# IO-testing-mezzanine.net
KiCad netlist of a schematic drawn in Altium Designer
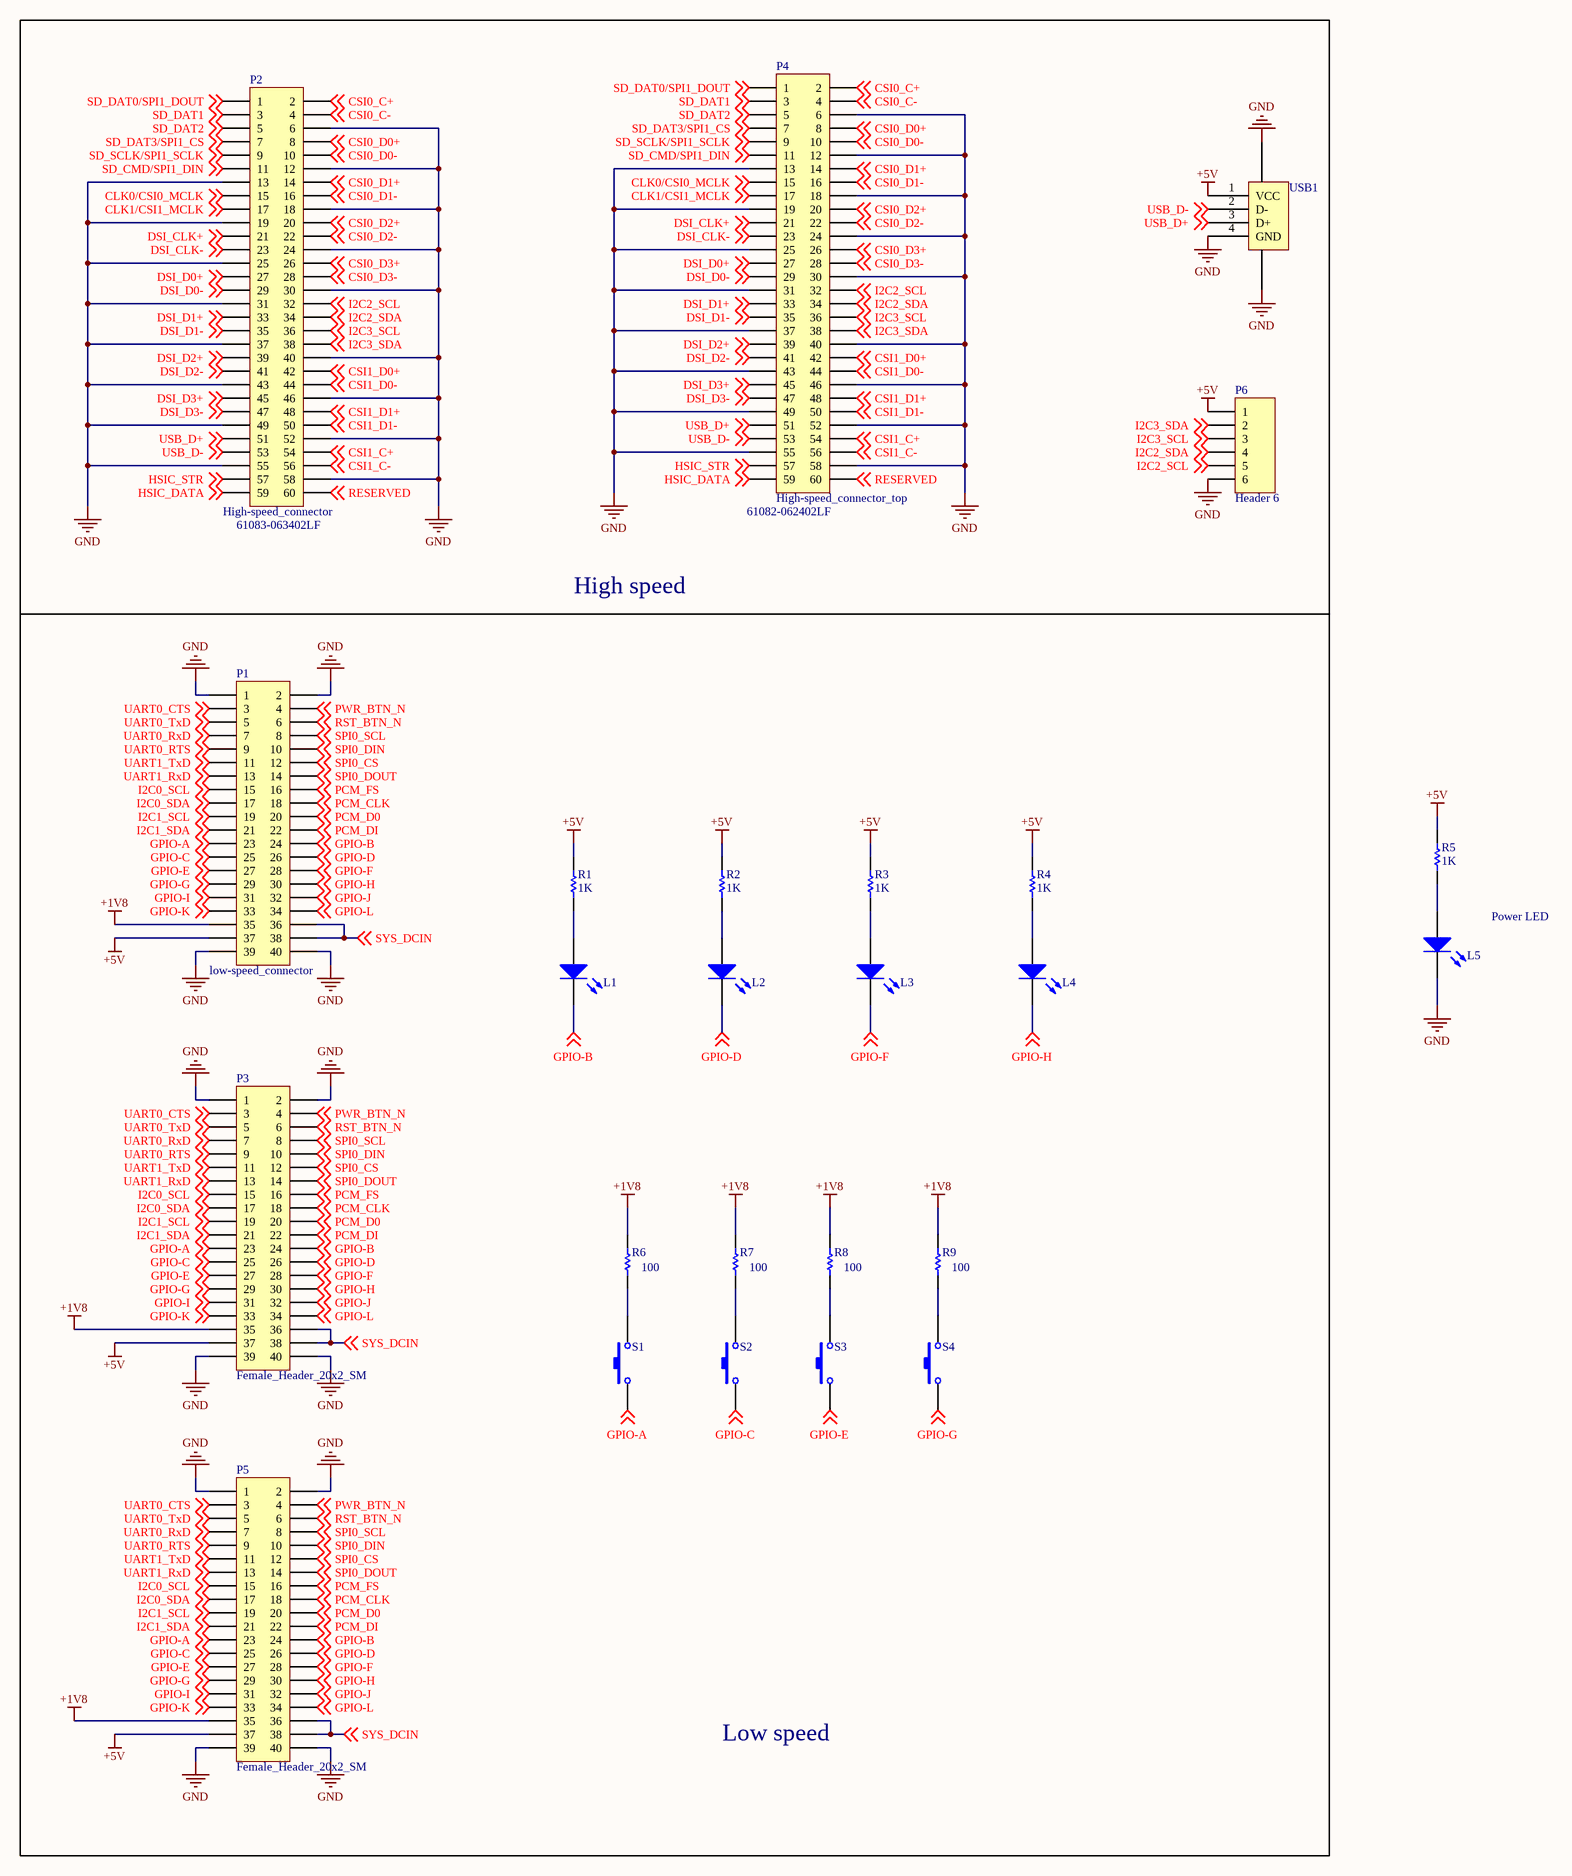
[diagram p0: IO-testing-mezzanine.SchDoc]

(export (version "E")
  (design (tool "Eeschema 10.0.6"))
  (components
    (comp (ref "L1")
      (value "~")
      (footprint "LED_0603")
      (description "LED BLUE CLEAR 0603 SMD")
      (fields
        (field (name "MANUFACTURER") "Lite-On Inc.")
        (field (name "MANUFACTURER PART NUMBER") "LTST-C193TBKT-5A")
      )
      (libsource (lib "IO-testing-mezzanine") (part "LTST-C193TBKT-5A"))
    )
    (comp (ref "L2")
      (value "~")
      (footprint "LED_0603")
      (description "LED BLUE CLEAR 0603 SMD")
      (fields
        (field (name "MANUFACTURER") "Lite-On Inc.")
        (field (name "MANUFACTURER PART NUMBER") "LTST-C193TBKT-5A")
      )
      (libsource (lib "IO-testing-mezzanine") (part "LTST-C193TBKT-5A"))
    )
    (comp (ref "L3")
      (value "~")
      (footprint "LED_0603")
      (description "LED BLUE CLEAR 0603 SMD")
      (fields
        (field (name "MANUFACTURER") "Lite-On Inc.")
        (field (name "MANUFACTURER PART NUMBER") "LTST-C193TBKT-5A")
      )
      (libsource (lib "IO-testing-mezzanine") (part "LTST-C193TBKT-5A"))
    )
    (comp (ref "L4")
      (value "~")
      (footprint "LED_0603")
      (description "LED BLUE CLEAR 0603 SMD")
      (fields
        (field (name "MANUFACTURER") "Lite-On Inc.")
        (field (name "MANUFACTURER PART NUMBER") "LTST-C193TBKT-5A")
      )
      (libsource (lib "IO-testing-mezzanine") (part "LTST-C193TBKT-5A"))
    )
    (comp (ref "L5")
      (value "~")
      (footprint "LED_0603")
      (description "LED BLUE CLEAR 0603 SMD")
      (fields
        (field (name "MANUFACTURER") "Lite-On Inc.")
        (field (name "MANUFACTURER PART NUMBER") "LTST-C193TBKT-5A")
      )
      (libsource (lib "IO-testing-mezzanine") (part "LTST-C193TBKT-5A"))
    )
    (comp (ref "P1")
      (value "low-speed_connector")
      (footprint "low-speed_connector_SM")
      (libsource (lib "mezza") (part "low-speed_connector"))
    )
    (comp (ref "P2")
      (value "High-speed_connector")
      (footprint "high-speed_connector")
      (fields (field (name "PARTNUMBER") "61083-063402LF"))
      (libsource (lib "mezza") (part "High-speed_connector"))
    )
    (comp (ref "P3")
      (value "Female_Header_20x2_SM")
      (footprint "Female_Header_20x2_SM")
      (libsource (lib "IO-testing-mezzanine") (part "Female_Header_20x2_SM"))
    )
    (comp (ref "P4")
      (value "High-speed_connector_top")
      (footprint "high-speed_connector_top")
      (fields
        (field (name "MANUFACTURER") "Amphenol FCI")
        (field (name "MANUFACTURER PART NUMBER") "61082-062402LF")
        (field (name "PARTNUMBER") "61082-062402LF")
      )
      (libsource (lib "IO-testing-mezzanine") (part "High-speed_connector_top"))
    )
    (comp (ref "P5")
      (value "Female_Header_20x2_SM")
      (footprint "low-speed_connector_SM_top")
      (libsource (lib "IO-testing-mezzanine") (part "Female_Header_20x2_SM"))
    )
    (comp (ref "P6")
      (value "Header 6")
      (footprint "HDR1X6")
      (description "Header, 6-Pin")
      (fields (field (name "PUBLISHER") "Altium Limited"))
      (libsource (lib "Miscellaneous Connectors") (part "Header 6"))
    )
    (comp (ref "R1")
      (value "1K")
      (footprint "0603")
      (description "Resistor")
      (fields
        (field (name "PARTNUMBER") "RC0603JR-071KL")
        (field (name "Comment") "Res1")
        (field (name "PUBLISHER") "Altium Limited")
      )
      (libsource (lib "IO-testing-mezzanine") (part "Res1"))
    )
    (comp (ref "R2")
      (value "1K")
      (footprint "0603")
      (description "Resistor")
      (fields
        (field (name "PARTNUMBER") "RC0603JR-071KL")
        (field (name "Comment") "Res1")
        (field (name "PUBLISHER") "Altium Limited")
      )
      (libsource (lib "IO-testing-mezzanine") (part "Res1"))
    )
    (comp (ref "R3")
      (value "1K")
      (footprint "0603")
      (description "Resistor")
      (fields
        (field (name "PARTNUMBER") "RC0603JR-071KL")
        (field (name "Comment") "Res1")
        (field (name "PUBLISHER") "Altium Limited")
      )
      (libsource (lib "IO-testing-mezzanine") (part "Res1"))
    )
    (comp (ref "R4")
      (value "1K")
      (footprint "0603")
      (description "Resistor")
      (fields
        (field (name "PARTNUMBER") "RC0603JR-071KL")
        (field (name "Comment") "Res1")
        (field (name "PUBLISHER") "Altium Limited")
      )
      (libsource (lib "IO-testing-mezzanine") (part "Res1"))
    )
    (comp (ref "R5")
      (value "1K")
      (footprint "0603")
      (description "Resistor")
      (fields
        (field (name "PARTNUMBER") "RC0603JR-071KL")
        (field (name "Comment") "Res1")
        (field (name "PUBLISHER") "Altium Limited")
      )
      (libsource (lib "IO-testing-mezzanine") (part "Res1"))
    )
    (comp (ref "R6")
      (value "100")
      (footprint "0603")
      (description "Resistor")
      (fields
        (field (name "MANUFACTURER") "Yageo")
        (field (name "MANUFACTURER PART NUMBER") "RC0603JR-07100RL")
      )
      (libsource (lib "IO-testing-mezzanine") (part "Res1"))
    )
    (comp (ref "R7")
      (value "100")
      (footprint "0603")
      (description "Resistor")
      (fields
        (field (name "MANUFACTURER") "Yageo")
        (field (name "MANUFACTURER PART NUMBER") "RC0603JR-07100RL")
      )
      (libsource (lib "IO-testing-mezzanine") (part "Res1"))
    )
    (comp (ref "R8")
      (value "100")
      (footprint "0603")
      (description "Resistor")
      (fields
        (field (name "MANUFACTURER") "Yageo")
        (field (name "MANUFACTURER PART NUMBER") "RC0603JR-07100RL")
      )
      (libsource (lib "IO-testing-mezzanine") (part "Res1"))
    )
    (comp (ref "R9")
      (value "100")
      (footprint "0603")
      (description "Resistor")
      (fields
        (field (name "MANUFACTURER") "Yageo")
        (field (name "MANUFACTURER PART NUMBER") "RC0603JR-07100RL")
      )
      (libsource (lib "IO-testing-mezzanine") (part "Res1"))
    )
    (comp (ref "S1")
      (value "SW-PB")
      (footprint "SW-PB")
      (description "Switch")
      (fields
        (field (name "MANUFACTURER") "C&K")
        (field (name "MANUFACTURER PART NUMBER") "KSR223GLFG")
        (field (name "PUBLISHER") "Altium Limited")
      )
      (libsource (lib "IO-testing-mezzanine") (part "SW-PB"))
    )
    (comp (ref "S2")
      (value "SW-PB")
      (footprint "SW-PB")
      (description "Switch")
      (fields
        (field (name "MANUFACTURER") "C&K")
        (field (name "MANUFACTURER PART NUMBER") "KSR223GLFG")
        (field (name "PUBLISHER") "Altium Limited")
      )
      (libsource (lib "IO-testing-mezzanine") (part "SW-PB"))
    )
    (comp (ref "S3")
      (value "SW-PB")
      (footprint "SW-PB")
      (description "Switch")
      (fields
        (field (name "MANUFACTURER") "C&K")
        (field (name "MANUFACTURER PART NUMBER") "KSR223GLFG")
        (field (name "PUBLISHER") "Altium Limited")
      )
      (libsource (lib "IO-testing-mezzanine") (part "SW-PB"))
    )
    (comp (ref "S4")
      (value "SW-PB")
      (footprint "SW-PB")
      (description "Switch")
      (fields
        (field (name "MANUFACTURER") "C&K")
        (field (name "MANUFACTURER PART NUMBER") "KSR223GLFG")
        (field (name "PUBLISHER") "Altium Limited")
      )
      (libsource (lib "IO-testing-mezzanine") (part "SW-PB"))
    )
    (comp (ref "USB1")
      (value "USB")
      (footprint "USB_a")
      (fields (field (name "PARTNUMBER") "USB-A-S-F-W-SM2") (field (name "MANUFACTURER") "Samtec Inc."))
      (libsource (lib "IO-testing-mezzanine") (part "USB"))
    )
  )
  (nets
    (net (code "1") (name "+1V8") (class "Default")
      (node (ref "P1") (pin "35") (pinfunction "35_35") (pintype "passive"))
      (node (ref "P3") (pin "35") (pinfunction "35_35") (pintype "passive"))
      (node (ref "P5") (pin "35") (pinfunction "35_35") (pintype "passive"))
      (node (ref "R6") (pin "2") (pinfunction "2_2") (pintype "passive"))
      (node (ref "R7") (pin "2") (pinfunction "2_2") (pintype "passive"))
      (node (ref "R8") (pin "2") (pinfunction "2_2") (pintype "passive"))
      (node (ref "R9") (pin "2") (pinfunction "2_2") (pintype "passive"))
    )
    (net (code "2") (name "+5V") (class "Default")
      (node (ref "P1") (pin "37") (pinfunction "37_37") (pintype "passive"))
      (node (ref "P3") (pin "37") (pinfunction "37_37") (pintype "passive"))
      (node (ref "P5") (pin "37") (pinfunction "37_37") (pintype "passive"))
      (node (ref "P6") (pin "1") (pinfunction "1_1") (pintype "passive"))
      (node (ref "R1") (pin "2") (pinfunction "2_2") (pintype "passive"))
      (node (ref "R2") (pin "2") (pinfunction "2_2") (pintype "passive"))
      (node (ref "R3") (pin "2") (pinfunction "2_2") (pintype "passive"))
      (node (ref "R4") (pin "2") (pinfunction "2_2") (pintype "passive"))
      (node (ref "R5") (pin "2") (pinfunction "2_2") (pintype "passive"))
      (node (ref "USB1") (pin "1") (pinfunction "VCC_1") (pintype "power_in"))
    )
    (net (code "3") (name "CLK0{slash}CSI0_MCLK") (class "Default")
      (node (ref "P2") (pin "15") (pinfunction "15_15") (pintype "passive"))
      (node (ref "P4") (pin "15") (pinfunction "15_15") (pintype "passive"))
    )
    (net (code "4") (name "CLK1{slash}CSI1_MCLK") (class "Default")
      (node (ref "P2") (pin "17") (pinfunction "17_17") (pintype "passive"))
      (node (ref "P4") (pin "17") (pinfunction "17_17") (pintype "passive"))
    )
    (net (code "5") (name "CSI0_C+") (class "Default")
      (node (ref "P2") (pin "2") (pinfunction "2_2") (pintype "passive"))
      (node (ref "P4") (pin "2") (pinfunction "2_2") (pintype "passive"))
    )
    (net (code "6") (name "CSI0_C-") (class "Default")
      (node (ref "P2") (pin "4") (pinfunction "4_4") (pintype "passive"))
      (node (ref "P4") (pin "4") (pinfunction "4_4") (pintype "passive"))
    )
    (net (code "7") (name "CSI0_D0+") (class "Default")
      (node (ref "P2") (pin "8") (pinfunction "8_8") (pintype "passive"))
      (node (ref "P4") (pin "8") (pinfunction "8_8") (pintype "passive"))
    )
    (net (code "8") (name "CSI0_D0-") (class "Default")
      (node (ref "P2") (pin "10") (pinfunction "10_10") (pintype "passive"))
      (node (ref "P4") (pin "10") (pinfunction "10_10") (pintype "passive"))
    )
    (net (code "9") (name "CSI0_D1+") (class "Default")
      (node (ref "P2") (pin "14") (pinfunction "14_14") (pintype "passive"))
      (node (ref "P4") (pin "14") (pinfunction "14_14") (pintype "passive"))
    )
    (net (code "10") (name "CSI0_D1-") (class "Default")
      (node (ref "P2") (pin "16") (pinfunction "16_16") (pintype "passive"))
      (node (ref "P4") (pin "16") (pinfunction "16_16") (pintype "passive"))
    )
    (net (code "11") (name "CSI0_D2+") (class "Default")
      (node (ref "P2") (pin "20") (pinfunction "20_20") (pintype "passive"))
      (node (ref "P4") (pin "20") (pinfunction "20_20") (pintype "passive"))
    )
    (net (code "12") (name "CSI0_D2-") (class "Default")
      (node (ref "P2") (pin "22") (pinfunction "22_22") (pintype "passive"))
      (node (ref "P4") (pin "22") (pinfunction "22_22") (pintype "passive"))
    )
    (net (code "13") (name "CSI0_D3+") (class "Default")
      (node (ref "P2") (pin "26") (pinfunction "26_26") (pintype "passive"))
      (node (ref "P4") (pin "26") (pinfunction "26_26") (pintype "passive"))
    )
    (net (code "14") (name "CSI0_D3-") (class "Default")
      (node (ref "P2") (pin "28") (pinfunction "28_28") (pintype "passive"))
      (node (ref "P4") (pin "28") (pinfunction "28_28") (pintype "passive"))
    )
    (net (code "15") (name "CSI1_C+") (class "Default")
      (node (ref "P2") (pin "54") (pinfunction "54_54") (pintype "passive"))
      (node (ref "P4") (pin "54") (pinfunction "54_54") (pintype "passive"))
    )
    (net (code "16") (name "CSI1_C-") (class "Default")
      (node (ref "P2") (pin "56") (pinfunction "56_56") (pintype "passive"))
      (node (ref "P4") (pin "56") (pinfunction "56_56") (pintype "passive"))
    )
    (net (code "17") (name "CSI1_D0+") (class "Default")
      (node (ref "P2") (pin "42") (pinfunction "42_42") (pintype "passive"))
      (node (ref "P4") (pin "42") (pinfunction "42_42") (pintype "passive"))
    )
    (net (code "18") (name "CSI1_D0-") (class "Default")
      (node (ref "P2") (pin "44") (pinfunction "44_44") (pintype "passive"))
      (node (ref "P4") (pin "44") (pinfunction "44_44") (pintype "passive"))
    )
    (net (code "19") (name "CSI1_D1+") (class "Default")
      (node (ref "P2") (pin "48") (pinfunction "48_48") (pintype "passive"))
      (node (ref "P4") (pin "48") (pinfunction "48_48") (pintype "passive"))
    )
    (net (code "20") (name "CSI1_D1-") (class "Default")
      (node (ref "P2") (pin "50") (pinfunction "50_50") (pintype "passive"))
      (node (ref "P4") (pin "50") (pinfunction "50_50") (pintype "passive"))
    )
    (net (code "21") (name "DSI_CLK+") (class "Default")
      (node (ref "P2") (pin "21") (pinfunction "21_21") (pintype "passive"))
      (node (ref "P4") (pin "21") (pinfunction "21_21") (pintype "passive"))
    )
    (net (code "22") (name "DSI_CLK-") (class "Default")
      (node (ref "P2") (pin "23") (pinfunction "23_23") (pintype "passive"))
      (node (ref "P4") (pin "23") (pinfunction "23_23") (pintype "passive"))
    )
    (net (code "23") (name "DSI_D0+") (class "Default")
      (node (ref "P2") (pin "27") (pinfunction "27_27") (pintype "passive"))
      (node (ref "P4") (pin "27") (pinfunction "27_27") (pintype "passive"))
    )
    (net (code "24") (name "DSI_D0-") (class "Default")
      (node (ref "P2") (pin "29") (pinfunction "29_29") (pintype "passive"))
      (node (ref "P4") (pin "29") (pinfunction "29_29") (pintype "passive"))
    )
    (net (code "25") (name "DSI_D1+") (class "Default")
      (node (ref "P2") (pin "33") (pinfunction "33_33") (pintype "passive"))
      (node (ref "P4") (pin "33") (pinfunction "33_33") (pintype "passive"))
    )
    (net (code "26") (name "DSI_D1-") (class "Default")
      (node (ref "P2") (pin "35") (pinfunction "35_35") (pintype "passive"))
      (node (ref "P4") (pin "35") (pinfunction "35_35") (pintype "passive"))
    )
    (net (code "27") (name "DSI_D2+") (class "Default")
      (node (ref "P2") (pin "39") (pinfunction "39_39") (pintype "passive"))
      (node (ref "P4") (pin "39") (pinfunction "39_39") (pintype "passive"))
    )
    (net (code "28") (name "DSI_D2-") (class "Default")
      (node (ref "P2") (pin "41") (pinfunction "41_41") (pintype "passive"))
      (node (ref "P4") (pin "41") (pinfunction "41_41") (pintype "passive"))
    )
    (net (code "29") (name "DSI_D3+") (class "Default")
      (node (ref "P2") (pin "45") (pinfunction "45_45") (pintype "passive"))
      (node (ref "P4") (pin "45") (pinfunction "45_45") (pintype "passive"))
    )
    (net (code "30") (name "DSI_D3-") (class "Default")
      (node (ref "P2") (pin "47") (pinfunction "47_47") (pintype "passive"))
      (node (ref "P4") (pin "47") (pinfunction "47_47") (pintype "passive"))
    )
    (net (code "31") (name "GND") (class "Default")
      (node (ref "L5") (pin "2") (pinfunction "K_2") (pintype "passive"))
      (node (ref "P1") (pin "1") (pinfunction "1_1") (pintype "passive"))
      (node (ref "P1") (pin "2") (pinfunction "2_2") (pintype "passive"))
      (node (ref "P1") (pin "39") (pinfunction "39_39") (pintype "passive"))
      (node (ref "P1") (pin "40") (pinfunction "40_40") (pintype "passive"))
      (node (ref "P2") (pin "12") (pinfunction "12_12") (pintype "passive"))
      (node (ref "P2") (pin "13") (pinfunction "13_13") (pintype "passive"))
      (node (ref "P2") (pin "18") (pinfunction "18_18") (pintype "passive"))
      (node (ref "P2") (pin "19") (pinfunction "19_19") (pintype "passive"))
      (node (ref "P2") (pin "24") (pinfunction "24_24") (pintype "passive"))
      (node (ref "P2") (pin "25") (pinfunction "25_25") (pintype "passive"))
      (node (ref "P2") (pin "30") (pinfunction "30_30") (pintype "passive"))
      (node (ref "P2") (pin "31") (pinfunction "31_31") (pintype "passive"))
      (node (ref "P2") (pin "37") (pinfunction "37_37") (pintype "passive"))
      (node (ref "P2") (pin "40") (pinfunction "40_40") (pintype "passive"))
      (node (ref "P2") (pin "43") (pinfunction "43_43") (pintype "passive"))
      (node (ref "P2") (pin "46") (pinfunction "46_46") (pintype "passive"))
      (node (ref "P2") (pin "49") (pinfunction "49_49") (pintype "passive"))
      (node (ref "P2") (pin "52") (pinfunction "52_52") (pintype "passive"))
      (node (ref "P2") (pin "55") (pinfunction "55_55") (pintype "passive"))
      (node (ref "P2") (pin "58") (pinfunction "58_58") (pintype "passive"))
      (node (ref "P2") (pin "6") (pinfunction "6_6") (pintype "passive"))
      (node (ref "P3") (pin "1") (pinfunction "1_1") (pintype "passive"))
      (node (ref "P3") (pin "2") (pinfunction "2_2") (pintype "passive"))
      (node (ref "P3") (pin "39") (pinfunction "39_39") (pintype "passive"))
      (node (ref "P3") (pin "40") (pinfunction "40_40") (pintype "passive"))
      (node (ref "P4") (pin "12") (pinfunction "12_12") (pintype "passive"))
      (node (ref "P4") (pin "13") (pinfunction "13_13") (pintype "passive"))
      (node (ref "P4") (pin "18") (pinfunction "18_18") (pintype "passive"))
      (node (ref "P4") (pin "19") (pinfunction "19_19") (pintype "passive"))
      (node (ref "P4") (pin "24") (pinfunction "24_24") (pintype "passive"))
      (node (ref "P4") (pin "25") (pinfunction "25_25") (pintype "passive"))
      (node (ref "P4") (pin "30") (pinfunction "30_30") (pintype "passive"))
      (node (ref "P4") (pin "31") (pinfunction "31_31") (pintype "passive"))
      (node (ref "P4") (pin "37") (pinfunction "37_37") (pintype "passive"))
      (node (ref "P4") (pin "40") (pinfunction "40_40") (pintype "passive"))
      (node (ref "P4") (pin "43") (pinfunction "43_43") (pintype "passive"))
      (node (ref "P4") (pin "46") (pinfunction "46_46") (pintype "passive"))
      (node (ref "P4") (pin "49") (pinfunction "49_49") (pintype "passive"))
      (node (ref "P4") (pin "52") (pinfunction "52_52") (pintype "passive"))
      (node (ref "P4") (pin "55") (pinfunction "55_55") (pintype "passive"))
      (node (ref "P4") (pin "58") (pinfunction "58_58") (pintype "passive"))
      (node (ref "P4") (pin "6") (pinfunction "6_6") (pintype "passive"))
      (node (ref "P5") (pin "1") (pinfunction "1_1") (pintype "passive"))
      (node (ref "P5") (pin "2") (pinfunction "2_2") (pintype "passive"))
      (node (ref "P5") (pin "39") (pinfunction "39_39") (pintype "passive"))
      (node (ref "P5") (pin "40") (pinfunction "40_40") (pintype "passive"))
      (node (ref "P6") (pin "6") (pinfunction "6_6") (pintype "passive"))
      (node (ref "USB1") (pin "4") (pinfunction "GND_4") (pintype "power_in"))
      (node (ref "USB1") (pin "5") (pinfunction "GND_5") (pintype "power_in"))
      (node (ref "USB1") (pin "6") (pinfunction "GND_6") (pintype "power_in"))
    )
    (net (code "32") (name "GPIO-A") (class "Default")
      (node (ref "P1") (pin "23") (pinfunction "23_23") (pintype "passive"))
      (node (ref "P3") (pin "23") (pinfunction "23_23") (pintype "passive"))
      (node (ref "P5") (pin "23") (pinfunction "23_23") (pintype "passive"))
      (node (ref "S1") (pin "1") (pinfunction "1_1") (pintype "passive"))
    )
    (net (code "33") (name "GPIO-B") (class "Default")
      (node (ref "L1") (pin "2") (pinfunction "K_2") (pintype "passive"))
      (node (ref "P1") (pin "24") (pinfunction "24_24") (pintype "passive"))
      (node (ref "P3") (pin "24") (pinfunction "24_24") (pintype "passive"))
      (node (ref "P5") (pin "24") (pinfunction "24_24") (pintype "passive"))
    )
    (net (code "34") (name "GPIO-C") (class "Default")
      (node (ref "P1") (pin "25") (pinfunction "25_25") (pintype "passive"))
      (node (ref "P3") (pin "25") (pinfunction "25_25") (pintype "passive"))
      (node (ref "P5") (pin "25") (pinfunction "25_25") (pintype "passive"))
      (node (ref "S2") (pin "1") (pinfunction "1_1") (pintype "passive"))
    )
    (net (code "35") (name "GPIO-D") (class "Default")
      (node (ref "L2") (pin "2") (pinfunction "K_2") (pintype "passive"))
      (node (ref "P1") (pin "26") (pinfunction "26_26") (pintype "passive"))
      (node (ref "P3") (pin "26") (pinfunction "26_26") (pintype "passive"))
      (node (ref "P5") (pin "26") (pinfunction "26_26") (pintype "passive"))
    )
    (net (code "36") (name "GPIO-E") (class "Default")
      (node (ref "P1") (pin "27") (pinfunction "27_27") (pintype "passive"))
      (node (ref "P3") (pin "27") (pinfunction "27_27") (pintype "passive"))
      (node (ref "P5") (pin "27") (pinfunction "27_27") (pintype "passive"))
      (node (ref "S3") (pin "1") (pinfunction "1_1") (pintype "passive"))
    )
    (net (code "37") (name "GPIO-F") (class "Default")
      (node (ref "L3") (pin "2") (pinfunction "K_2") (pintype "passive"))
      (node (ref "P1") (pin "28") (pinfunction "28_28") (pintype "passive"))
      (node (ref "P3") (pin "28") (pinfunction "28_28") (pintype "passive"))
      (node (ref "P5") (pin "28") (pinfunction "28_28") (pintype "passive"))
    )
    (net (code "38") (name "GPIO-G") (class "Default")
      (node (ref "P1") (pin "29") (pinfunction "29_29") (pintype "passive"))
      (node (ref "P3") (pin "29") (pinfunction "29_29") (pintype "passive"))
      (node (ref "P5") (pin "29") (pinfunction "29_29") (pintype "passive"))
      (node (ref "S4") (pin "1") (pinfunction "1_1") (pintype "passive"))
    )
    (net (code "39") (name "GPIO-H") (class "Default")
      (node (ref "L4") (pin "2") (pinfunction "K_2") (pintype "passive"))
      (node (ref "P1") (pin "30") (pinfunction "30_30") (pintype "passive"))
      (node (ref "P3") (pin "30") (pinfunction "30_30") (pintype "passive"))
      (node (ref "P5") (pin "30") (pinfunction "30_30") (pintype "passive"))
    )
    (net (code "40") (name "GPIO-I") (class "Default")
      (node (ref "P1") (pin "31") (pinfunction "31_31") (pintype "passive"))
      (node (ref "P3") (pin "31") (pinfunction "31_31") (pintype "passive"))
      (node (ref "P5") (pin "31") (pinfunction "31_31") (pintype "passive"))
    )
    (net (code "41") (name "GPIO-J") (class "Default")
      (node (ref "P1") (pin "32") (pinfunction "32_32") (pintype "passive"))
      (node (ref "P3") (pin "32") (pinfunction "32_32") (pintype "passive"))
      (node (ref "P5") (pin "32") (pinfunction "32_32") (pintype "passive"))
    )
    (net (code "42") (name "GPIO-K") (class "Default")
      (node (ref "P1") (pin "33") (pinfunction "33_33") (pintype "passive"))
      (node (ref "P3") (pin "33") (pinfunction "33_33") (pintype "passive"))
      (node (ref "P5") (pin "33") (pinfunction "33_33") (pintype "passive"))
    )
    (net (code "43") (name "GPIO-L") (class "Default")
      (node (ref "P1") (pin "34") (pinfunction "34_34") (pintype "passive"))
      (node (ref "P3") (pin "34") (pinfunction "34_34") (pintype "passive"))
      (node (ref "P5") (pin "34") (pinfunction "34_34") (pintype "passive"))
    )
    (net (code "44") (name "HSIC_DATA") (class "Default")
      (node (ref "P2") (pin "59") (pinfunction "59_59") (pintype "passive"))
      (node (ref "P4") (pin "59") (pinfunction "59_59") (pintype "passive"))
    )
    (net (code "45") (name "HSIC_STR") (class "Default")
      (node (ref "P2") (pin "39") (pinfunction "57_39") (pintype "passive"))
      (node (ref "P4") (pin "39") (pinfunction "57_39") (pintype "passive"))
    )
    (net (code "46") (name "I2C0_SCL") (class "Default")
      (node (ref "P1") (pin "15") (pinfunction "15_15") (pintype "passive"))
      (node (ref "P3") (pin "15") (pinfunction "15_15") (pintype "passive"))
      (node (ref "P5") (pin "15") (pinfunction "15_15") (pintype "passive"))
    )
    (net (code "47") (name "I2C0_SDA") (class "Default")
      (node (ref "P1") (pin "17") (pinfunction "17_17") (pintype "passive"))
      (node (ref "P3") (pin "17") (pinfunction "17_17") (pintype "passive"))
      (node (ref "P5") (pin "17") (pinfunction "17_17") (pintype "passive"))
    )
    (net (code "48") (name "I2C1_SCL") (class "Default")
      (node (ref "P1") (pin "19") (pinfunction "19_19") (pintype "passive"))
      (node (ref "P3") (pin "19") (pinfunction "19_19") (pintype "passive"))
      (node (ref "P5") (pin "19") (pinfunction "19_19") (pintype "passive"))
    )
    (net (code "49") (name "I2C1_SDA") (class "Default")
      (node (ref "P1") (pin "21") (pinfunction "21_21") (pintype "passive"))
      (node (ref "P3") (pin "21") (pinfunction "21_21") (pintype "passive"))
      (node (ref "P5") (pin "21") (pinfunction "21_21") (pintype "passive"))
    )
    (net (code "50") (name "I2C2_SCL") (class "Default")
      (node (ref "P2") (pin "32") (pinfunction "32_32") (pintype "passive"))
      (node (ref "P4") (pin "32") (pinfunction "32_32") (pintype "passive"))
      (node (ref "P6") (pin "5") (pinfunction "5_5") (pintype "passive"))
    )
    (net (code "51") (name "I2C2_SDA") (class "Default")
      (node (ref "P2") (pin "34") (pinfunction "34_34") (pintype "passive"))
      (node (ref "P4") (pin "34") (pinfunction "34_34") (pintype "passive"))
      (node (ref "P6") (pin "4") (pinfunction "4_4") (pintype "passive"))
    )
    (net (code "52") (name "I2C3_SCL") (class "Default")
      (node (ref "P2") (pin "36") (pinfunction "36_36") (pintype "passive"))
      (node (ref "P4") (pin "36") (pinfunction "36_36") (pintype "passive"))
      (node (ref "P6") (pin "3") (pinfunction "3_3") (pintype "passive"))
    )
    (net (code "53") (name "I2C3_SDA") (class "Default")
      (node (ref "P2") (pin "38") (pinfunction "38_38") (pintype "passive"))
      (node (ref "P4") (pin "38") (pinfunction "38_38") (pintype "passive"))
      (node (ref "P6") (pin "2") (pinfunction "2_2") (pintype "passive"))
    )
    (net (code "54") (name "Net-(L1-A)") (class "Default")
      (node (ref "L1") (pin "1") (pinfunction "A_1") (pintype "passive"))
      (node (ref "R1") (pin "1") (pinfunction "1_1") (pintype "passive"))
    )
    (net (code "55") (name "Net-(L2-A)") (class "Default")
      (node (ref "L2") (pin "1") (pinfunction "A_1") (pintype "passive"))
      (node (ref "R2") (pin "1") (pinfunction "1_1") (pintype "passive"))
    )
    (net (code "56") (name "Net-(L3-A)") (class "Default")
      (node (ref "L3") (pin "1") (pinfunction "A_1") (pintype "passive"))
      (node (ref "R3") (pin "1") (pinfunction "1_1") (pintype "passive"))
    )
    (net (code "57") (name "Net-(L4-A)") (class "Default")
      (node (ref "L4") (pin "1") (pinfunction "A_1") (pintype "passive"))
      (node (ref "R4") (pin "1") (pinfunction "1_1") (pintype "passive"))
    )
    (net (code "58") (name "Net-(L5-A)") (class "Default")
      (node (ref "L5") (pin "1") (pinfunction "A_1") (pintype "passive"))
      (node (ref "R5") (pin "1") (pinfunction "1_1") (pintype "passive"))
    )
    (net (code "59") (name "Net-(R6-Pad1)") (class "Default")
      (node (ref "R6") (pin "1") (pinfunction "1_1") (pintype "passive"))
      (node (ref "S1") (pin "2") (pinfunction "2_2") (pintype "passive"))
    )
    (net (code "60") (name "Net-(R7-Pad1)") (class "Default")
      (node (ref "R7") (pin "1") (pinfunction "1_1") (pintype "passive"))
      (node (ref "S2") (pin "2") (pinfunction "2_2") (pintype "passive"))
    )
    (net (code "61") (name "Net-(R8-Pad1)") (class "Default")
      (node (ref "R8") (pin "1") (pinfunction "1_1") (pintype "passive"))
      (node (ref "S3") (pin "2") (pinfunction "2_2") (pintype "passive"))
    )
    (net (code "62") (name "Net-(R9-Pad1)") (class "Default")
      (node (ref "R9") (pin "1") (pinfunction "1_1") (pintype "passive"))
      (node (ref "S4") (pin "2") (pinfunction "2_2") (pintype "passive"))
    )
    (net (code "63") (name "PCM_CLK") (class "Default")
      (node (ref "P1") (pin "18") (pinfunction "18_18") (pintype "passive"))
      (node (ref "P3") (pin "18") (pinfunction "18_18") (pintype "passive"))
      (node (ref "P5") (pin "18") (pinfunction "18_18") (pintype "passive"))
    )
    (net (code "64") (name "PCM_D0") (class "Default")
      (node (ref "P1") (pin "20") (pinfunction "20_20") (pintype "passive"))
      (node (ref "P3") (pin "20") (pinfunction "20_20") (pintype "passive"))
      (node (ref "P5") (pin "20") (pinfunction "20_20") (pintype "passive"))
    )
    (net (code "65") (name "PCM_DI") (class "Default")
      (node (ref "P1") (pin "22") (pinfunction "22_22") (pintype "passive"))
      (node (ref "P3") (pin "22") (pinfunction "22_22") (pintype "passive"))
      (node (ref "P5") (pin "22") (pinfunction "22_22") (pintype "passive"))
    )
    (net (code "66") (name "PCM_FS") (class "Default")
      (node (ref "P1") (pin "16") (pinfunction "16_16") (pintype "passive"))
      (node (ref "P3") (pin "16") (pinfunction "16_16") (pintype "passive"))
      (node (ref "P5") (pin "16") (pinfunction "16_16") (pintype "passive"))
    )
    (net (code "67") (name "PWR_BTN_N") (class "Default")
      (node (ref "P1") (pin "4") (pinfunction "4_4") (pintype "passive"))
      (node (ref "P3") (pin "4") (pinfunction "4_4") (pintype "passive"))
      (node (ref "P5") (pin "4") (pinfunction "4_4") (pintype "passive"))
    )
    (net (code "68") (name "RESERVED") (class "Default")
      (node (ref "P2") (pin "38") (pinfunction "60_38") (pintype "passive"))
      (node (ref "P4") (pin "38") (pinfunction "60_38") (pintype "passive"))
    )
    (net (code "69") (name "RST_BTN_N") (class "Default")
      (node (ref "P1") (pin "6") (pinfunction "6_6") (pintype "passive"))
      (node (ref "P3") (pin "6") (pinfunction "6_6") (pintype "passive"))
      (node (ref "P5") (pin "6") (pinfunction "6_6") (pintype "passive"))
    )
    (net (code "70") (name "SD_CMD{slash}SPI1_DIN") (class "Default")
      (node (ref "P2") (pin "11") (pinfunction "11_11") (pintype "passive"))
      (node (ref "P4") (pin "11") (pinfunction "11_11") (pintype "passive"))
    )
    (net (code "71") (name "SD_DAT0{slash}SPI1_DOUT") (class "Default")
      (node (ref "P2") (pin "1") (pinfunction "1_1") (pintype "passive"))
      (node (ref "P4") (pin "1") (pinfunction "1_1") (pintype "passive"))
    )
    (net (code "72") (name "SD_DAT1") (class "Default")
      (node (ref "P2") (pin "3") (pinfunction "3_3") (pintype "passive"))
      (node (ref "P4") (pin "3") (pinfunction "3_3") (pintype "passive"))
    )
    (net (code "73") (name "SD_DAT2") (class "Default")
      (node (ref "P2") (pin "5") (pinfunction "5_5") (pintype "passive"))
      (node (ref "P4") (pin "5") (pinfunction "5_5") (pintype "passive"))
    )
    (net (code "74") (name "SD_DAT3{slash}SPI1_CS") (class "Default")
      (node (ref "P2") (pin "7") (pinfunction "7_7") (pintype "passive"))
      (node (ref "P4") (pin "7") (pinfunction "7_7") (pintype "passive"))
    )
    (net (code "75") (name "SD_SCLK{slash}SPI1_SCLK") (class "Default")
      (node (ref "P2") (pin "9") (pinfunction "9_9") (pintype "passive"))
      (node (ref "P4") (pin "9") (pinfunction "9_9") (pintype "passive"))
    )
    (net (code "76") (name "SPI0_CS") (class "Default")
      (node (ref "P1") (pin "12") (pinfunction "12_12") (pintype "passive"))
      (node (ref "P3") (pin "12") (pinfunction "12_12") (pintype "passive"))
      (node (ref "P5") (pin "12") (pinfunction "12_12") (pintype "passive"))
    )
    (net (code "77") (name "SPI0_DIN") (class "Default")
      (node (ref "P1") (pin "10") (pinfunction "10_10") (pintype "passive"))
      (node (ref "P3") (pin "10") (pinfunction "10_10") (pintype "passive"))
      (node (ref "P5") (pin "10") (pinfunction "10_10") (pintype "passive"))
    )
    (net (code "78") (name "SPI0_DOUT") (class "Default")
      (node (ref "P1") (pin "14") (pinfunction "14_14") (pintype "passive"))
      (node (ref "P3") (pin "14") (pinfunction "14_14") (pintype "passive"))
      (node (ref "P5") (pin "14") (pinfunction "14_14") (pintype "passive"))
    )
    (net (code "79") (name "SPI0_SCL") (class "Default")
      (node (ref "P1") (pin "8") (pinfunction "8_8") (pintype "passive"))
      (node (ref "P3") (pin "8") (pinfunction "8_8") (pintype "passive"))
      (node (ref "P5") (pin "8") (pinfunction "8_8") (pintype "passive"))
    )
    (net (code "80") (name "SYS_DCIN") (class "Default")
      (node (ref "P1") (pin "36") (pinfunction "36_36") (pintype "passive"))
      (node (ref "P1") (pin "38") (pinfunction "38_38") (pintype "passive"))
      (node (ref "P3") (pin "36") (pinfunction "36_36") (pintype "passive"))
      (node (ref "P3") (pin "38") (pinfunction "38_38") (pintype "passive"))
      (node (ref "P5") (pin "36") (pinfunction "36_36") (pintype "passive"))
      (node (ref "P5") (pin "38") (pinfunction "38_38") (pintype "passive"))
    )
    (net (code "81") (name "UART0_CTS") (class "Default")
      (node (ref "P1") (pin "3") (pinfunction "3_3") (pintype "passive"))
      (node (ref "P3") (pin "3") (pinfunction "3_3") (pintype "passive"))
      (node (ref "P5") (pin "3") (pinfunction "3_3") (pintype "passive"))
    )
    (net (code "82") (name "UART0_RTS") (class "Default")
      (node (ref "P1") (pin "9") (pinfunction "9_9") (pintype "passive"))
      (node (ref "P3") (pin "9") (pinfunction "9_9") (pintype "passive"))
      (node (ref "P5") (pin "9") (pinfunction "9_9") (pintype "passive"))
    )
    (net (code "83") (name "UART0_RxD") (class "Default")
      (node (ref "P1") (pin "7") (pinfunction "7_7") (pintype "passive"))
      (node (ref "P3") (pin "7") (pinfunction "7_7") (pintype "passive"))
      (node (ref "P5") (pin "7") (pinfunction "7_7") (pintype "passive"))
    )
    (net (code "84") (name "UART0_TxD") (class "Default")
      (node (ref "P1") (pin "5") (pinfunction "5_5") (pintype "passive"))
      (node (ref "P3") (pin "5") (pinfunction "5_5") (pintype "passive"))
      (node (ref "P5") (pin "5") (pinfunction "5_5") (pintype "passive"))
    )
    (net (code "85") (name "UART1_RxD") (class "Default")
      (node (ref "P1") (pin "13") (pinfunction "13_13") (pintype "passive"))
      (node (ref "P3") (pin "13") (pinfunction "13_13") (pintype "passive"))
      (node (ref "P5") (pin "13") (pinfunction "13_13") (pintype "passive"))
    )
    (net (code "86") (name "UART1_TxD") (class "Default")
      (node (ref "P1") (pin "11") (pinfunction "11_11") (pintype "passive"))
      (node (ref "P3") (pin "11") (pinfunction "11_11") (pintype "passive"))
      (node (ref "P5") (pin "11") (pinfunction "11_11") (pintype "passive"))
    )
    (net (code "87") (name "USB_D+") (class "Default")
      (node (ref "P2") (pin "51") (pinfunction "51_51") (pintype "passive"))
      (node (ref "P4") (pin "51") (pinfunction "51_51") (pintype "passive"))
      (node (ref "USB1") (pin "3") (pinfunction "D+_3") (pintype "passive"))
    )
    (net (code "88") (name "USB_D-") (class "Default")
      (node (ref "P2") (pin "53") (pinfunction "53_53") (pintype "passive"))
      (node (ref "P4") (pin "53") (pinfunction "53_53") (pintype "passive"))
      (node (ref "USB1") (pin "2") (pinfunction "D-_2") (pintype "passive"))
    )
  )
)
